# LPRD_Valve_Control_V2_1.net
KiCad netlist of a schematic drawn in EAGLE
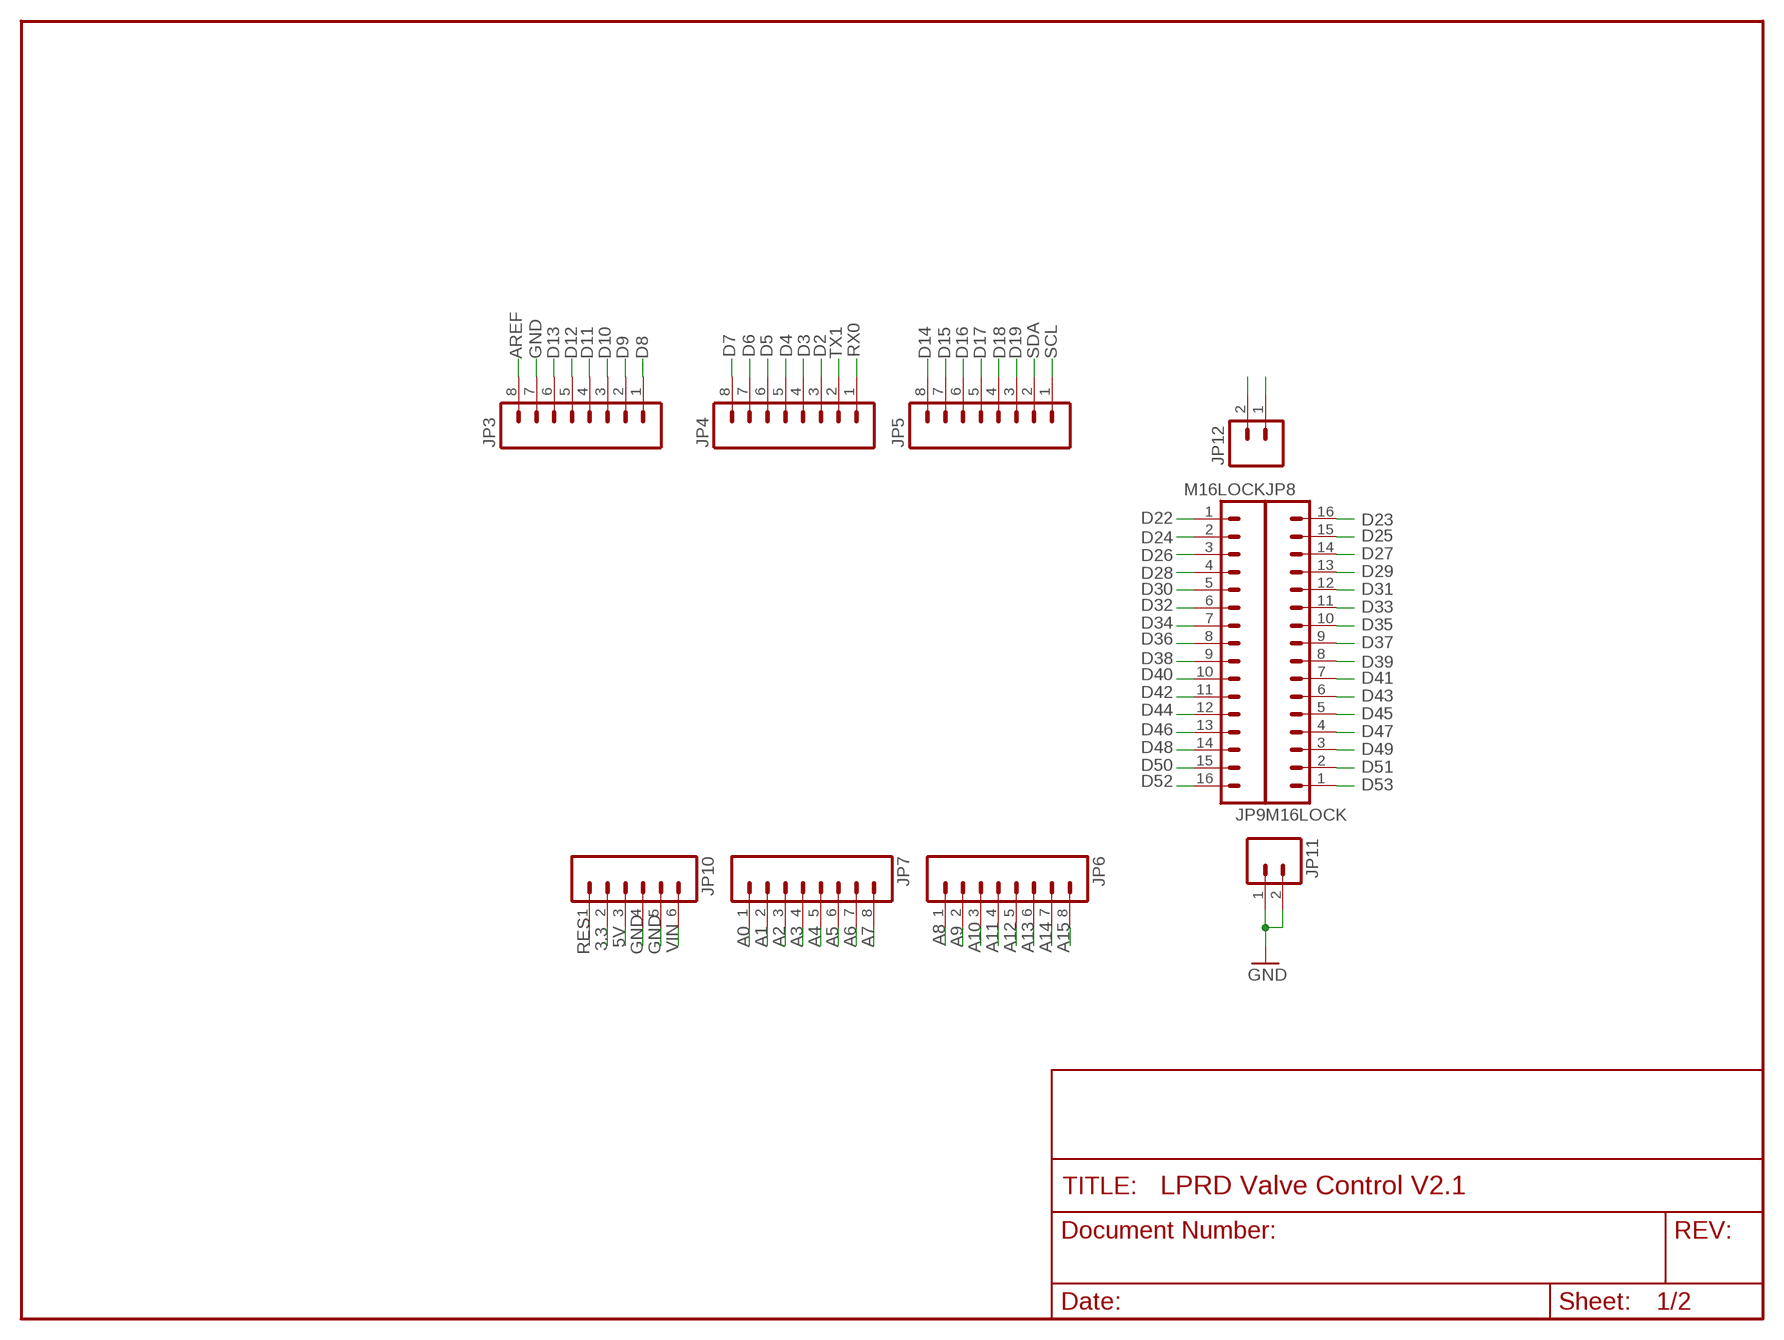
[diagram p0: schematic, sheet 1]
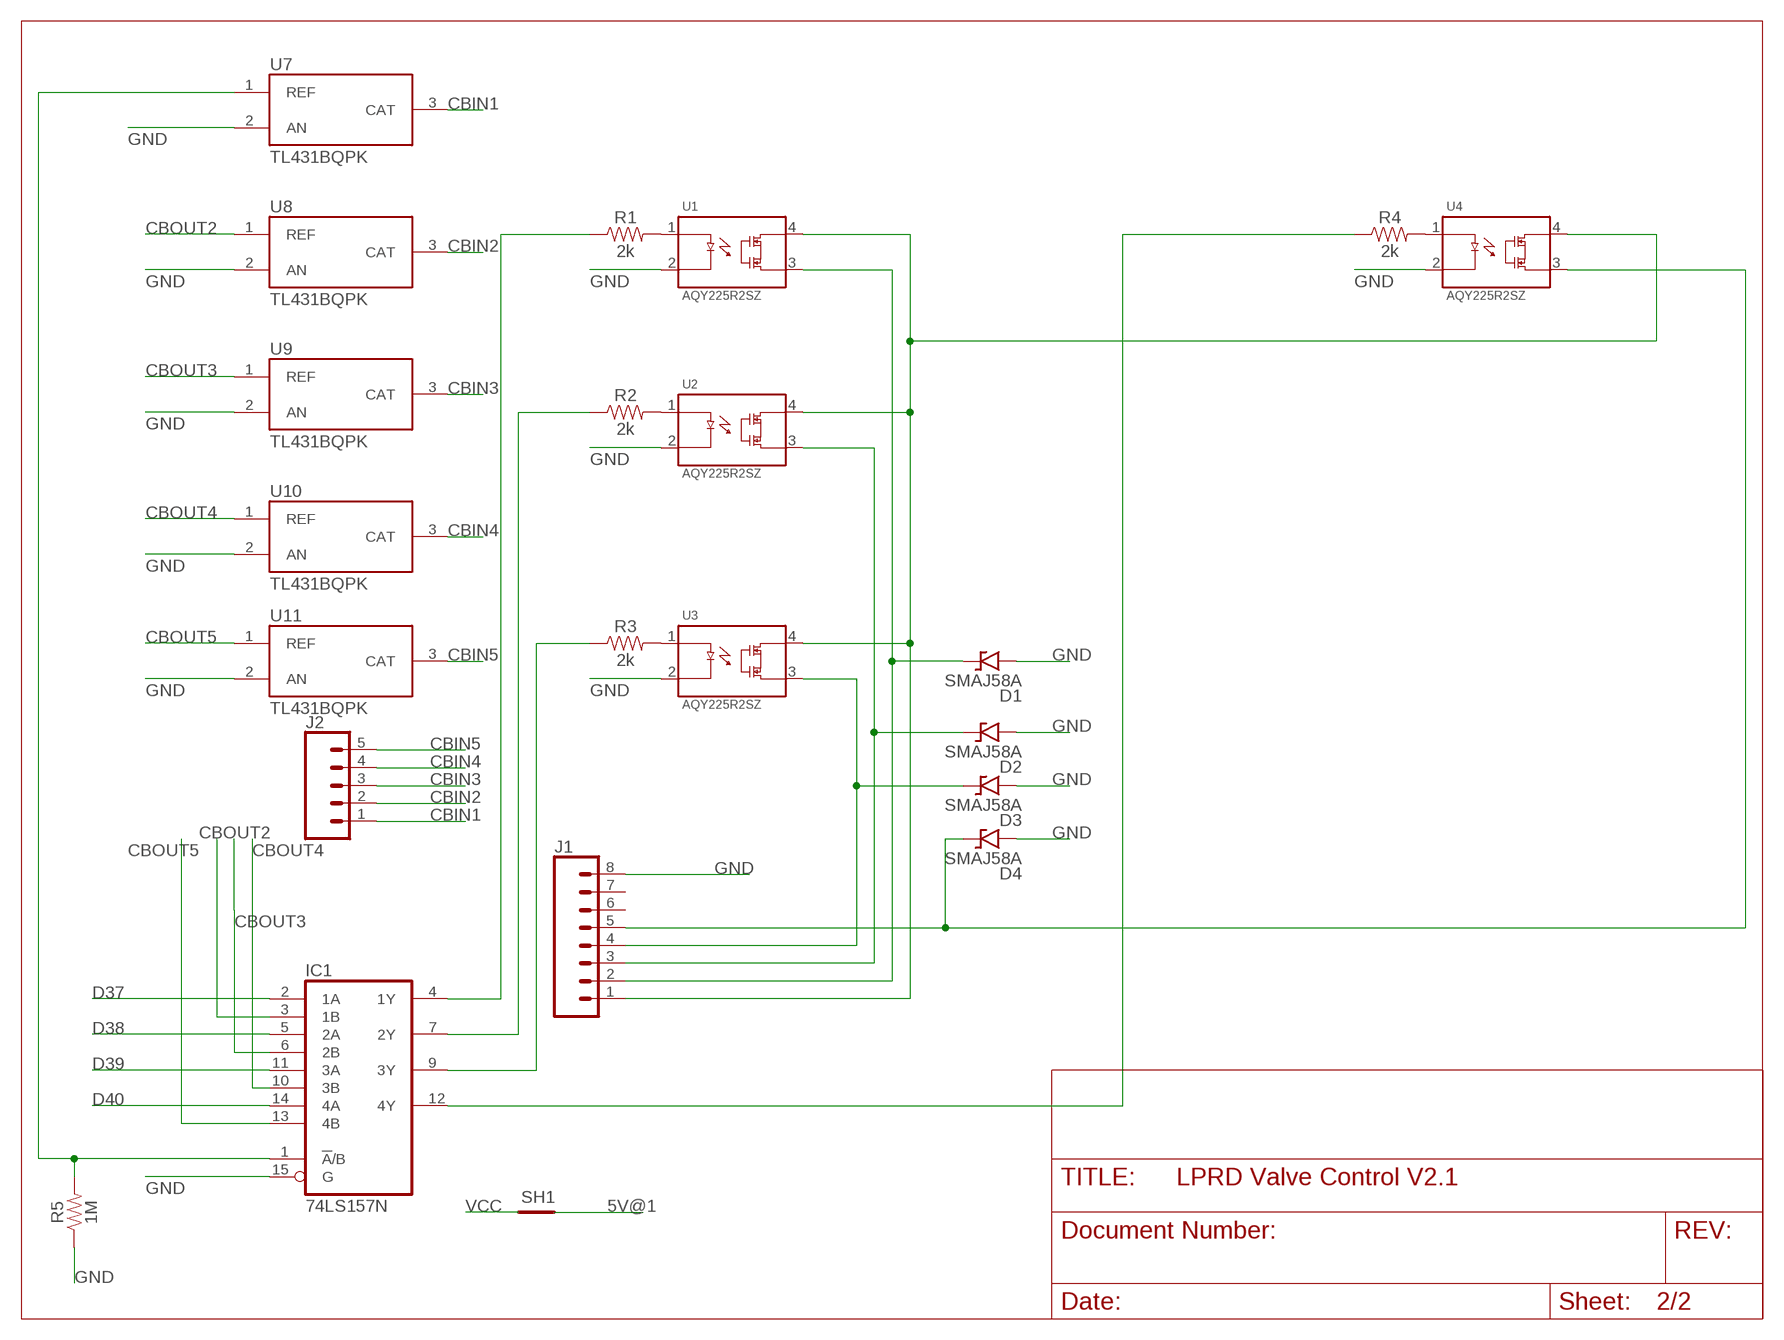
[diagram p1: schematic, sheet 2]

(export (version "E")
  (design (tool "Eeschema 10.0.6"))
  (components
    (comp (ref "JP3")
      (value "M08LOCK")
      (footprint "eagle-import:1X08_LOCK")
      (libsource (lib "eagle-import") (part "M08LOCK"))
    )
    (comp (ref "JP4")
      (value "M08LOCK")
      (footprint "eagle-import:1X08_LOCK")
      (libsource (lib "eagle-import") (part "M08LOCK"))
    )
    (comp (ref "JP5")
      (value "M08LOCK")
      (footprint "eagle-import:1X08_LOCK")
      (libsource (lib "eagle-import") (part "M08LOCK"))
    )
    (comp (ref "JP6")
      (value "M08LOCK")
      (footprint "eagle-import:1X08_LOCK")
      (libsource (lib "eagle-import") (part "M08LOCK"))
    )
    (comp (ref "JP7")
      (value "M08LOCK")
      (footprint "eagle-import:1X08_LOCK")
      (libsource (lib "eagle-import") (part "M08LOCK"))
    )
    (comp (ref "JP8")
      (value "M16LOCK")
      (footprint "eagle-import:1X16_LOCK")
      (libsource (lib "eagle-import") (part "M16LOCK"))
    )
    (comp (ref "JP9")
      (value "M16LOCK")
      (footprint "eagle-import:1X16_LOCK")
      (libsource (lib "eagle-import") (part "M16LOCK"))
    )
    (comp (ref "JP10")
      (value "M06LOCK")
      (footprint "eagle-import:1X06_LOCK")
      (libsource (lib "eagle-import") (part "M06LOCK"))
    )
    (comp (ref "JP11")
      (value "M02LOCK")
      (footprint "eagle-import:1X02_LOCK")
      (libsource (lib "eagle-import") (part "M02LOCK"))
    )
    (comp (ref "JP12")
      (value "M02LOCK")
      (footprint "eagle-import:1X02_LOCK")
      (libsource (lib "eagle-import") (part "M02LOCK"))
    )
    (comp (ref "D1")
      (value "SMAJ58A")
      (footprint "eagle-import:SMA")
      (fields (field (name "DIGI-KEY_PART_NUMBER") "SMAJ58ABTR-ND") (field (name "MF") "Bourns"))
      (libsource (lib "eagle-import") (part "SMAJ58A"))
    )
    (comp (ref "D2")
      (value "SMAJ58A")
      (footprint "eagle-import:SMA")
      (fields (field (name "DIGI-KEY_PART_NUMBER") "SMAJ58ABTR-ND") (field (name "MF") "Bourns"))
      (libsource (lib "eagle-import") (part "SMAJ58A"))
    )
    (comp (ref "D3")
      (value "SMAJ58A")
      (footprint "eagle-import:SMA")
      (fields (field (name "DIGI-KEY_PART_NUMBER") "SMAJ58ABTR-ND") (field (name "MF") "Bourns"))
      (libsource (lib "eagle-import") (part "SMAJ58A"))
    )
    (comp (ref "D4")
      (value "SMAJ58A")
      (footprint "eagle-import:SMA")
      (fields (field (name "DIGI-KEY_PART_NUMBER") "SMAJ58ABTR-ND") (field (name "MF") "Bourns"))
      (libsource (lib "eagle-import") (part "SMAJ58A"))
    )
    (comp (ref "IC1")
      (value "74LS157N")
      (footprint "eagle-import:DIL16")
      (libsource (lib "eagle-import") (part "74157NLS"))
    )
    (comp (ref "J1")
      (value "CONN_08\"")
      (footprint "eagle-import:1X08")
      (libsource (lib "eagle-import") (part "CONN_08{dblquote}"))
    )
    (comp (ref "J2")
      (value "CONN_05")
      (footprint "eagle-import:1X05")
      (libsource (lib "eagle-import") (part "CONN_05"))
    )
    (comp (ref "R1")
      (value "2k")
      (footprint "eagle-import:0805")
      (libsource (lib "eagle-import") (part "RESISTOR0805"))
    )
    (comp (ref "R2")
      (value "2k")
      (footprint "eagle-import:0805")
      (libsource (lib "eagle-import") (part "RESISTOR0805"))
    )
    (comp (ref "R3")
      (value "2k")
      (footprint "eagle-import:0805")
      (libsource (lib "eagle-import") (part "RESISTOR0805"))
    )
    (comp (ref "R4")
      (value "2k")
      (footprint "eagle-import:0805")
      (libsource (lib "eagle-import") (part "RESISTOR0805"))
    )
    (comp (ref "R5")
      (value "1M")
      (footprint "eagle-import:0805")
      (libsource (lib "eagle-import") (part "RESISTOR0805"))
    )
    (comp (ref "SH1")
      (value "SHORTT5")
      (footprint "eagle-import:SHORT_TOP-50")
      (libsource (lib "eagle-import") (part "SHORTT5"))
    )
    (comp (ref "U1")
      (value "AQY225R2SZ")
      (footprint "eagle-import:SOIC254P680X220-4N")
      (fields (field (name "DIGI-KEY_PART_NUMBER") "AQY225R2SZ-ND") (field (name "MF") "Panasonic"))
      (libsource (lib "eagle-import") (part "AQY225R2SZ"))
    )
    (comp (ref "U2")
      (value "AQY225R2SZ")
      (footprint "eagle-import:SOIC254P680X220-4N")
      (fields (field (name "DIGI-KEY_PART_NUMBER") "AQY225R2SZ-ND") (field (name "MF") "Panasonic"))
      (libsource (lib "eagle-import") (part "AQY225R2SZ"))
    )
    (comp (ref "U3")
      (value "AQY225R2SZ")
      (footprint "eagle-import:SOIC254P680X220-4N")
      (fields (field (name "DIGI-KEY_PART_NUMBER") "AQY225R2SZ-ND") (field (name "MF") "Panasonic"))
      (libsource (lib "eagle-import") (part "AQY225R2SZ"))
    )
    (comp (ref "U4")
      (value "AQY225R2SZ")
      (footprint "eagle-import:SOIC254P680X220-4N")
      (fields (field (name "DIGI-KEY_PART_NUMBER") "AQY225R2SZ-ND") (field (name "MF") "Panasonic"))
      (libsource (lib "eagle-import") (part "AQY225R2SZ"))
    )
    (comp (ref "U7")
      (value "TL431BQPK")
      (footprint "eagle-import:VREG_TL431BQPK")
      (fields (field (name "MF") "Texas Instruments"))
      (libsource (lib "eagle-import") (part "TL431BQPK"))
    )
    (comp (ref "U8")
      (value "TL431BQPK")
      (footprint "eagle-import:VREG_TL431BQPK")
      (fields (field (name "MF") "Texas Instruments"))
      (libsource (lib "eagle-import") (part "TL431BQPK"))
    )
    (comp (ref "U9")
      (value "TL431BQPK")
      (footprint "eagle-import:VREG_TL431BQPK")
      (fields (field (name "MF") "Texas Instruments"))
      (libsource (lib "eagle-import") (part "TL431BQPK"))
    )
    (comp (ref "U10")
      (value "TL431BQPK")
      (footprint "eagle-import:VREG_TL431BQPK")
      (fields (field (name "MF") "Texas Instruments"))
      (libsource (lib "eagle-import") (part "TL431BQPK"))
    )
    (comp (ref "U11")
      (value "TL431BQPK")
      (footprint "eagle-import:VREG_TL431BQPK")
      (fields (field (name "MF") "Texas Instruments"))
      (libsource (lib "eagle-import") (part "TL431BQPK"))
    )
  )
  (nets
    (net (code "1") (name "3.3") (class "Default")
      (node (ref "JP10") (pin "2") (pinfunction "2_2") (pintype "passive"))
    )
    (net (code "2") (name "5V") (class "Default")
      (node (ref "JP10") (pin "3") (pinfunction "3_3") (pintype "passive"))
    )
    (net (code "3") (name "5V@1") (class "Default")
      (node (ref "JP12") (pin "1") (pinfunction "1_1") (pintype "passive"))
      (node (ref "JP12") (pin "2") (pinfunction "2_2") (pintype "passive"))
      (node (ref "SH1") (pin "2") (pinfunction "P$2_2") (pintype "bidirectional"))
    )
    (net (code "4") (name "A0") (class "Default")
      (node (ref "JP7") (pin "1") (pinfunction "1_1") (pintype "passive"))
    )
    (net (code "5") (name "A1") (class "Default")
      (node (ref "JP7") (pin "2") (pinfunction "2_2") (pintype "passive"))
    )
    (net (code "6") (name "A2") (class "Default")
      (node (ref "JP7") (pin "3") (pinfunction "3_3") (pintype "passive"))
    )
    (net (code "7") (name "A3") (class "Default")
      (node (ref "JP7") (pin "4") (pinfunction "4_4") (pintype "passive"))
    )
    (net (code "8") (name "A4") (class "Default")
      (node (ref "JP7") (pin "5") (pinfunction "5_5") (pintype "passive"))
    )
    (net (code "9") (name "A5") (class "Default")
      (node (ref "JP7") (pin "6") (pinfunction "6_6") (pintype "passive"))
    )
    (net (code "10") (name "A6") (class "Default")
      (node (ref "JP7") (pin "7") (pinfunction "7_7") (pintype "passive"))
    )
    (net (code "11") (name "A7") (class "Default")
      (node (ref "JP7") (pin "8") (pinfunction "8_8") (pintype "passive"))
    )
    (net (code "12") (name "A8") (class "Default")
      (node (ref "JP6") (pin "1") (pinfunction "1_1") (pintype "passive"))
    )
    (net (code "13") (name "A9") (class "Default")
      (node (ref "JP6") (pin "2") (pinfunction "2_2") (pintype "passive"))
    )
    (net (code "14") (name "A10") (class "Default")
      (node (ref "JP6") (pin "3") (pinfunction "3_3") (pintype "passive"))
    )
    (net (code "15") (name "A11") (class "Default")
      (node (ref "JP6") (pin "4") (pinfunction "4_4") (pintype "passive"))
    )
    (net (code "16") (name "A12") (class "Default")
      (node (ref "JP6") (pin "5") (pinfunction "5_5") (pintype "passive"))
    )
    (net (code "17") (name "A13") (class "Default")
      (node (ref "JP6") (pin "6") (pinfunction "6_6") (pintype "passive"))
    )
    (net (code "18") (name "A14") (class "Default")
      (node (ref "JP6") (pin "7") (pinfunction "7_7") (pintype "passive"))
    )
    (net (code "19") (name "A15") (class "Default")
      (node (ref "JP6") (pin "8") (pinfunction "8_8") (pintype "passive"))
    )
    (net (code "20") (name "AREF") (class "Default")
      (node (ref "JP3") (pin "8") (pinfunction "8_8") (pintype "passive"))
    )
    (net (code "21") (name "CBIN1") (class "Default")
      (node (ref "J2") (pin "1") (pinfunction "1_1") (pintype "passive"))
      (node (ref "U7") (pin "3") (pinfunction "CAT_3") (pintype "output"))
    )
    (net (code "22") (name "CBIN2") (class "Default")
      (node (ref "J2") (pin "2") (pinfunction "2_2") (pintype "passive"))
      (node (ref "U8") (pin "3") (pinfunction "CAT_3") (pintype "output"))
    )
    (net (code "23") (name "CBIN3") (class "Default")
      (node (ref "J2") (pin "3") (pinfunction "3_3") (pintype "passive"))
      (node (ref "U9") (pin "3") (pinfunction "CAT_3") (pintype "output"))
    )
    (net (code "24") (name "CBIN4") (class "Default")
      (node (ref "J2") (pin "4") (pinfunction "4_4") (pintype "passive"))
      (node (ref "U10") (pin "3") (pinfunction "CAT_3") (pintype "output"))
    )
    (net (code "25") (name "CBIN5") (class "Default")
      (node (ref "J2") (pin "5") (pinfunction "5_5") (pintype "passive"))
      (node (ref "U11") (pin "3") (pinfunction "CAT_3") (pintype "output"))
    )
    (net (code "26") (name "CBOUT2") (class "Default")
      (node (ref "IC1") (pin "3") (pinfunction "1B_3") (pintype "input"))
      (node (ref "U8") (pin "1") (pinfunction "REF_1") (pintype "input"))
    )
    (net (code "27") (name "CBOUT3") (class "Default")
      (node (ref "IC1") (pin "6") (pinfunction "2B_6") (pintype "input"))
      (node (ref "U9") (pin "1") (pinfunction "REF_1") (pintype "input"))
    )
    (net (code "28") (name "CBOUT4") (class "Default")
      (node (ref "IC1") (pin "10") (pinfunction "3B_10") (pintype "input"))
      (node (ref "U10") (pin "1") (pinfunction "REF_1") (pintype "input"))
    )
    (net (code "29") (name "CBOUT5") (class "Default")
      (node (ref "IC1") (pin "13") (pinfunction "4B_13") (pintype "input"))
      (node (ref "U11") (pin "1") (pinfunction "REF_1") (pintype "input"))
    )
    (net (code "30") (name "D2") (class "Default")
      (node (ref "JP4") (pin "3") (pinfunction "3_3") (pintype "passive"))
    )
    (net (code "31") (name "D3") (class "Default")
      (node (ref "JP4") (pin "4") (pinfunction "4_4") (pintype "passive"))
    )
    (net (code "32") (name "D4") (class "Default")
      (node (ref "JP4") (pin "5") (pinfunction "5_5") (pintype "passive"))
    )
    (net (code "33") (name "D5") (class "Default")
      (node (ref "JP4") (pin "6") (pinfunction "6_6") (pintype "passive"))
    )
    (net (code "34") (name "D6") (class "Default")
      (node (ref "JP4") (pin "7") (pinfunction "7_7") (pintype "passive"))
    )
    (net (code "35") (name "D7") (class "Default")
      (node (ref "JP4") (pin "8") (pinfunction "8_8") (pintype "passive"))
    )
    (net (code "36") (name "D8") (class "Default")
      (node (ref "JP3") (pin "1") (pinfunction "1_1") (pintype "passive"))
    )
    (net (code "37") (name "D9") (class "Default")
      (node (ref "JP3") (pin "2") (pinfunction "2_2") (pintype "passive"))
    )
    (net (code "38") (name "D10") (class "Default")
      (node (ref "JP3") (pin "3") (pinfunction "3_3") (pintype "passive"))
    )
    (net (code "39") (name "D11") (class "Default")
      (node (ref "JP3") (pin "4") (pinfunction "4_4") (pintype "passive"))
    )
    (net (code "40") (name "D12") (class "Default")
      (node (ref "JP3") (pin "5") (pinfunction "5_5") (pintype "passive"))
    )
    (net (code "41") (name "D13") (class "Default")
      (node (ref "JP3") (pin "6") (pinfunction "6_6") (pintype "passive"))
    )
    (net (code "42") (name "D14") (class "Default")
      (node (ref "JP5") (pin "8") (pinfunction "8_8") (pintype "passive"))
    )
    (net (code "43") (name "D15") (class "Default")
      (node (ref "JP5") (pin "7") (pinfunction "7_7") (pintype "passive"))
    )
    (net (code "44") (name "D16") (class "Default")
      (node (ref "JP5") (pin "6") (pinfunction "6_6") (pintype "passive"))
    )
    (net (code "45") (name "D17") (class "Default")
      (node (ref "JP5") (pin "5") (pinfunction "5_5") (pintype "passive"))
    )
    (net (code "46") (name "D18") (class "Default")
      (node (ref "JP5") (pin "4") (pinfunction "4_4") (pintype "passive"))
    )
    (net (code "47") (name "D19") (class "Default")
      (node (ref "JP5") (pin "3") (pinfunction "3_3") (pintype "passive"))
    )
    (net (code "48") (name "D22") (class "Default")
      (node (ref "JP9") (pin "1") (pinfunction "1_1") (pintype "passive"))
    )
    (net (code "49") (name "D23") (class "Default")
      (node (ref "JP8") (pin "16") (pinfunction "16_16") (pintype "passive"))
    )
    (net (code "50") (name "D24") (class "Default")
      (node (ref "JP9") (pin "2") (pinfunction "2_2") (pintype "passive"))
    )
    (net (code "51") (name "D25") (class "Default")
      (node (ref "JP8") (pin "15") (pinfunction "15_15") (pintype "passive"))
    )
    (net (code "52") (name "D26") (class "Default")
      (node (ref "JP9") (pin "3") (pinfunction "3_3") (pintype "passive"))
    )
    (net (code "53") (name "D27") (class "Default")
      (node (ref "JP8") (pin "14") (pinfunction "14_14") (pintype "passive"))
    )
    (net (code "54") (name "D28") (class "Default")
      (node (ref "JP9") (pin "4") (pinfunction "4_4") (pintype "passive"))
    )
    (net (code "55") (name "D29") (class "Default")
      (node (ref "JP8") (pin "13") (pinfunction "13_13") (pintype "passive"))
    )
    (net (code "56") (name "D30") (class "Default")
      (node (ref "JP9") (pin "5") (pinfunction "5_5") (pintype "passive"))
    )
    (net (code "57") (name "D31") (class "Default")
      (node (ref "JP8") (pin "12") (pinfunction "12_12") (pintype "passive"))
    )
    (net (code "58") (name "D32") (class "Default")
      (node (ref "JP9") (pin "6") (pinfunction "6_6") (pintype "passive"))
    )
    (net (code "59") (name "D33") (class "Default")
      (node (ref "JP8") (pin "11") (pinfunction "11_11") (pintype "passive"))
    )
    (net (code "60") (name "D34") (class "Default")
      (node (ref "JP9") (pin "7") (pinfunction "7_7") (pintype "passive"))
    )
    (net (code "61") (name "D35") (class "Default")
      (node (ref "JP8") (pin "10") (pinfunction "10_10") (pintype "passive"))
    )
    (net (code "62") (name "D36") (class "Default")
      (node (ref "JP9") (pin "8") (pinfunction "8_8") (pintype "passive"))
    )
    (net (code "63") (name "D37") (class "Default")
      (node (ref "IC1") (pin "2") (pinfunction "1A_2") (pintype "input"))
      (node (ref "JP8") (pin "9") (pinfunction "9_9") (pintype "passive"))
    )
    (net (code "64") (name "D38") (class "Default")
      (node (ref "IC1") (pin "5") (pinfunction "2A_5") (pintype "input"))
      (node (ref "JP9") (pin "9") (pinfunction "9_9") (pintype "passive"))
    )
    (net (code "65") (name "D39") (class "Default")
      (node (ref "IC1") (pin "11") (pinfunction "3A_11") (pintype "input"))
      (node (ref "JP8") (pin "8") (pinfunction "8_8") (pintype "passive"))
    )
    (net (code "66") (name "D40") (class "Default")
      (node (ref "IC1") (pin "14") (pinfunction "4A_14") (pintype "input"))
      (node (ref "JP9") (pin "10") (pinfunction "10_10") (pintype "passive"))
    )
    (net (code "67") (name "D41") (class "Default")
      (node (ref "JP8") (pin "7") (pinfunction "7_7") (pintype "passive"))
    )
    (net (code "68") (name "D42") (class "Default")
      (node (ref "JP9") (pin "11") (pinfunction "11_11") (pintype "passive"))
    )
    (net (code "69") (name "D43") (class "Default")
      (node (ref "JP8") (pin "6") (pinfunction "6_6") (pintype "passive"))
    )
    (net (code "70") (name "D44") (class "Default")
      (node (ref "JP9") (pin "12") (pinfunction "12_12") (pintype "passive"))
    )
    (net (code "71") (name "D45") (class "Default")
      (node (ref "JP8") (pin "5") (pinfunction "5_5") (pintype "passive"))
    )
    (net (code "72") (name "D46") (class "Default")
      (node (ref "JP9") (pin "13") (pinfunction "13_13") (pintype "passive"))
    )
    (net (code "73") (name "D47") (class "Default")
      (node (ref "JP8") (pin "4") (pinfunction "4_4") (pintype "passive"))
    )
    (net (code "74") (name "D48") (class "Default")
      (node (ref "JP9") (pin "14") (pinfunction "14_14") (pintype "passive"))
    )
    (net (code "75") (name "D49") (class "Default")
      (node (ref "JP8") (pin "3") (pinfunction "3_3") (pintype "passive"))
    )
    (net (code "76") (name "D50") (class "Default")
      (node (ref "JP9") (pin "15") (pinfunction "15_15") (pintype "passive"))
    )
    (net (code "77") (name "D51") (class "Default")
      (node (ref "JP8") (pin "2") (pinfunction "2_2") (pintype "passive"))
    )
    (net (code "78") (name "D52") (class "Default")
      (node (ref "JP9") (pin "16") (pinfunction "16_16") (pintype "passive"))
    )
    (net (code "79") (name "D53") (class "Default")
      (node (ref "JP8") (pin "1") (pinfunction "1_1") (pintype "passive"))
    )
    (net (code "80") (name "GND") (class "Default")
      (node (ref "D1") (pin "A") (pinfunction "A_A") (pintype "passive"))
      (node (ref "D2") (pin "A") (pinfunction "A_A") (pintype "passive"))
      (node (ref "D3") (pin "A") (pinfunction "A_A") (pintype "passive"))
      (node (ref "D4") (pin "A") (pinfunction "A_A") (pintype "passive"))
      (node (ref "IC1") (pin "15") (pinfunction "G_15") (pintype "input"))
      (node (ref "J1") (pin "8") (pinfunction "8_8") (pintype "passive"))
      (node (ref "JP10") (pin "4") (pinfunction "4_4") (pintype "passive"))
      (node (ref "JP10") (pin "5") (pinfunction "5_5") (pintype "passive"))
      (node (ref "JP11") (pin "1") (pinfunction "1_1") (pintype "passive"))
      (node (ref "JP11") (pin "2") (pinfunction "2_2") (pintype "passive"))
      (node (ref "JP3") (pin "7") (pinfunction "7_7") (pintype "passive"))
      (node (ref "R5") (pin "1") (pinfunction "1_1") (pintype "passive"))
      (node (ref "U1") (pin "2") (pinfunction "2_2") (pintype "passive"))
      (node (ref "U10") (pin "2") (pinfunction "AN_2") (pintype "bidirectional"))
      (node (ref "U11") (pin "2") (pinfunction "AN_2") (pintype "bidirectional"))
      (node (ref "U2") (pin "2") (pinfunction "2_2") (pintype "passive"))
      (node (ref "U3") (pin "2") (pinfunction "2_2") (pintype "passive"))
      (node (ref "U4") (pin "2") (pinfunction "2_2") (pintype "passive"))
      (node (ref "U7") (pin "2") (pinfunction "AN_2") (pintype "bidirectional"))
      (node (ref "U8") (pin "2") (pinfunction "AN_2") (pintype "bidirectional"))
      (node (ref "U9") (pin "2") (pinfunction "AN_2") (pintype "bidirectional"))
    )
    (net (code "81") (name "Net-(D1-PadC)") (class "Default")
      (node (ref "D1") (pin "C") (pinfunction "C_C") (pintype "passive"))
      (node (ref "J1") (pin "2") (pinfunction "2_2") (pintype "passive"))
      (node (ref "U1") (pin "3") (pinfunction "3_3") (pintype "passive"))
    )
    (net (code "82") (name "Net-(D2-PadC)") (class "Default")
      (node (ref "D2") (pin "C") (pinfunction "C_C") (pintype "passive"))
      (node (ref "J1") (pin "3") (pinfunction "3_3") (pintype "passive"))
      (node (ref "U2") (pin "3") (pinfunction "3_3") (pintype "passive"))
    )
    (net (code "83") (name "Net-(D3-PadC)") (class "Default")
      (node (ref "D3") (pin "C") (pinfunction "C_C") (pintype "passive"))
      (node (ref "J1") (pin "4") (pinfunction "4_4") (pintype "passive"))
      (node (ref "U3") (pin "3") (pinfunction "3_3") (pintype "passive"))
    )
    (net (code "84") (name "Net-(D4-PadC)") (class "Default")
      (node (ref "D4") (pin "C") (pinfunction "C_C") (pintype "passive"))
      (node (ref "J1") (pin "5") (pinfunction "5_5") (pintype "passive"))
      (node (ref "U4") (pin "3") (pinfunction "3_3") (pintype "passive"))
    )
    (net (code "85") (name "Net-(IC1A-1Y)") (class "Default")
      (node (ref "IC1") (pin "4") (pinfunction "1Y_4") (pintype "output"))
      (node (ref "R1") (pin "1") (pinfunction "1_1") (pintype "passive"))
    )
    (net (code "86") (name "Net-(IC1A-2Y)") (class "Default")
      (node (ref "IC1") (pin "7") (pinfunction "2Y_7") (pintype "output"))
      (node (ref "R2") (pin "1") (pinfunction "1_1") (pintype "passive"))
    )
    (net (code "87") (name "Net-(IC1A-3Y)") (class "Default")
      (node (ref "IC1") (pin "9") (pinfunction "3Y_9") (pintype "output"))
      (node (ref "R3") (pin "1") (pinfunction "1_1") (pintype "passive"))
    )
    (net (code "88") (name "Net-(IC1A-4Y)") (class "Default")
      (node (ref "IC1") (pin "12") (pinfunction "4Y_12") (pintype "output"))
      (node (ref "R4") (pin "1") (pinfunction "1_1") (pintype "passive"))
    )
    (net (code "89") (name "Net-(IC1A-~{A}{slash}B)") (class "Default")
      (node (ref "IC1") (pin "1") (pinfunction "~{A}/B_1") (pintype "input"))
      (node (ref "R5") (pin "2") (pinfunction "2_2") (pintype "passive"))
      (node (ref "U7") (pin "1") (pinfunction "REF_1") (pintype "input"))
    )
    (net (code "90") (name "Net-(J1-Pad1)") (class "Default")
      (node (ref "J1") (pin "1") (pinfunction "1_1") (pintype "passive"))
      (node (ref "U1") (pin "4") (pinfunction "4_4") (pintype "passive"))
      (node (ref "U2") (pin "4") (pinfunction "4_4") (pintype "passive"))
      (node (ref "U3") (pin "4") (pinfunction "4_4") (pintype "passive"))
      (node (ref "U4") (pin "4") (pinfunction "4_4") (pintype "passive"))
    )
    (net (code "91") (name "Net-(R1-Pad2)") (class "Default")
      (node (ref "R1") (pin "2") (pinfunction "2_2") (pintype "passive"))
      (node (ref "U1") (pin "1") (pinfunction "1_1") (pintype "passive"))
    )
    (net (code "92") (name "Net-(R2-Pad2)") (class "Default")
      (node (ref "R2") (pin "2") (pinfunction "2_2") (pintype "passive"))
      (node (ref "U2") (pin "1") (pinfunction "1_1") (pintype "passive"))
    )
    (net (code "93") (name "Net-(R3-Pad2)") (class "Default")
      (node (ref "R3") (pin "2") (pinfunction "2_2") (pintype "passive"))
      (node (ref "U3") (pin "1") (pinfunction "1_1") (pintype "passive"))
    )
    (net (code "94") (name "Net-(R4-Pad2)") (class "Default")
      (node (ref "R4") (pin "2") (pinfunction "2_2") (pintype "passive"))
      (node (ref "U4") (pin "1") (pinfunction "1_1") (pintype "passive"))
    )
    (net (code "95") (name "RES") (class "Default")
      (node (ref "JP10") (pin "1") (pinfunction "1_1") (pintype "passive"))
    )
    (net (code "96") (name "RX0") (class "Default")
      (node (ref "JP4") (pin "1") (pinfunction "1_1") (pintype "passive"))
    )
    (net (code "97") (name "SCL") (class "Default")
      (node (ref "JP5") (pin "1") (pinfunction "1_1") (pintype "passive"))
    )
    (net (code "98") (name "SDA") (class "Default")
      (node (ref "JP5") (pin "2") (pinfunction "2_2") (pintype "passive"))
    )
    (net (code "99") (name "TX1") (class "Default")
      (node (ref "JP4") (pin "2") (pinfunction "2_2") (pintype "passive"))
    )
    (net (code "100") (name "VCC") (class "Default")
      (node (ref "SH1") (pin "1") (pinfunction "P$1_1") (pintype "bidirectional"))
    )
    (net (code "101") (name "VIN") (class "Default")
      (node (ref "JP10") (pin "6") (pinfunction "6_6") (pintype "passive"))
    )
    (net (code "102") (name "unconnected-(J1-Pad6)") (class "Default")
      (node (ref "J1") (pin "6") (pinfunction "6_6") (pintype "passive"))
    )
    (net (code "103") (name "unconnected-(J1-Pad7)") (class "Default")
      (node (ref "J1") (pin "7") (pinfunction "7_7") (pintype "passive"))
    )
  )
)
